# BPF.net
KiCad netlist of a schematic drawn in Altium Designer
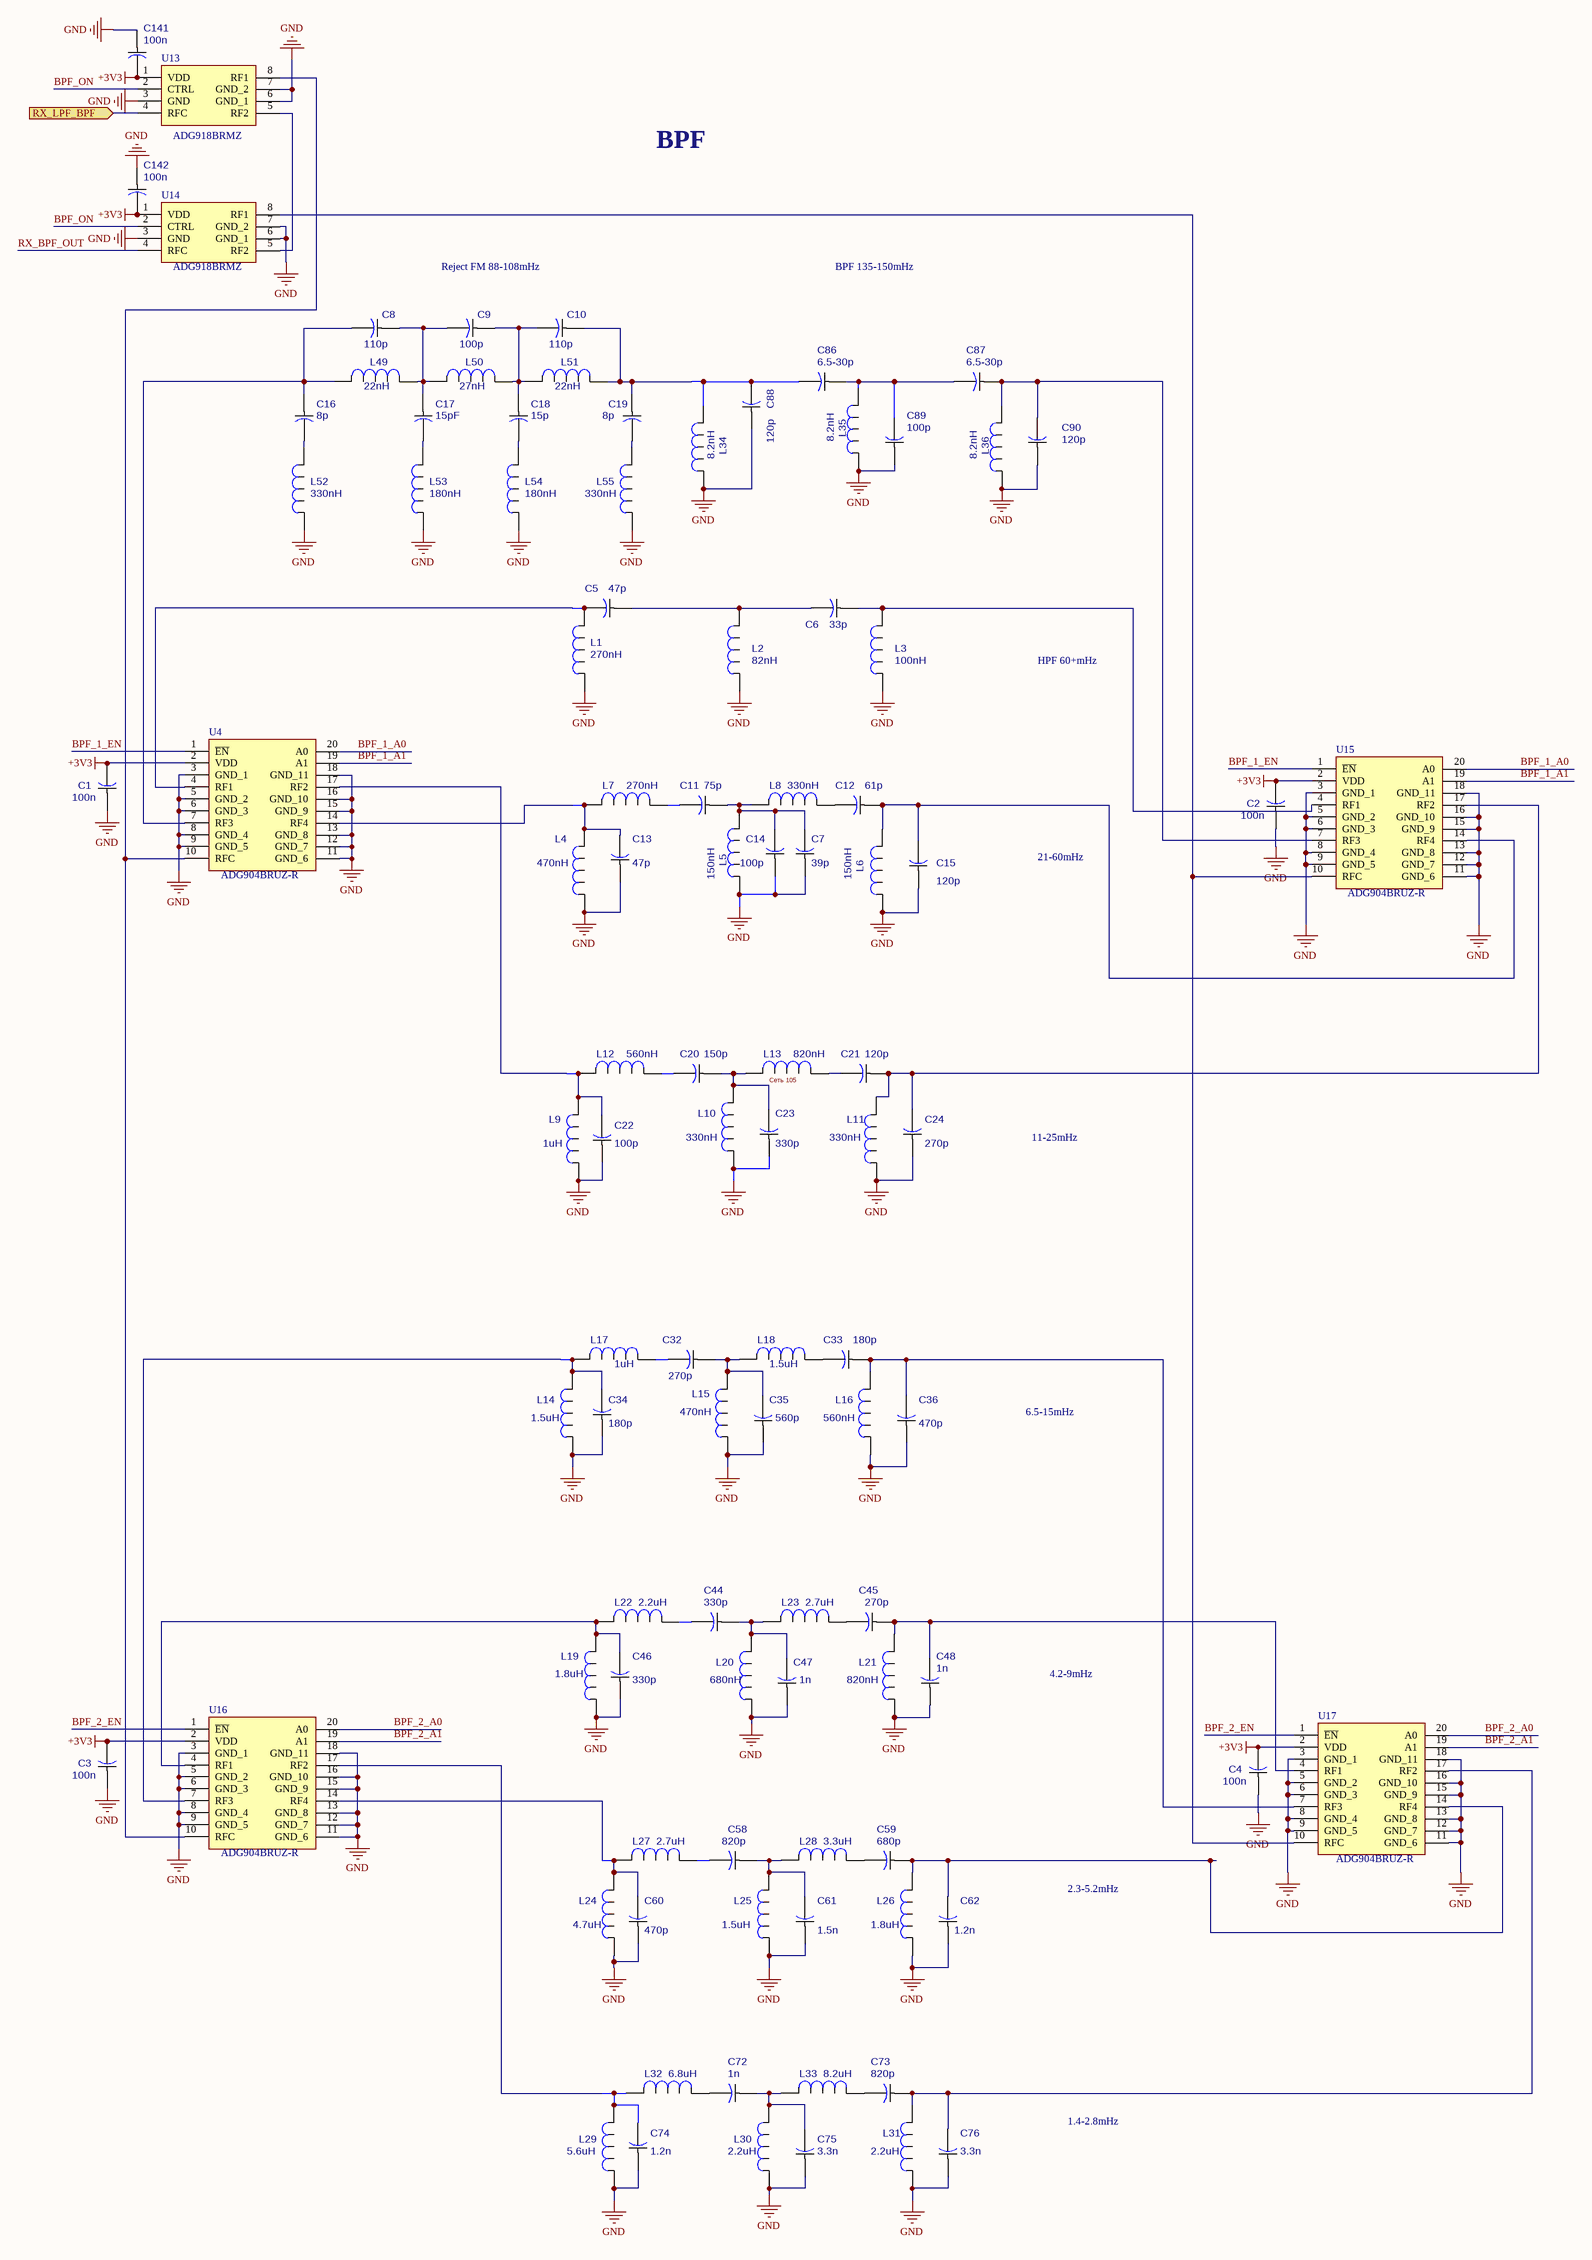
[diagram p0: BPF.SchDoc]

(export (version "E")
  (design (tool "Eeschema 10.0.6"))
  (components
    (comp (ref "C1")
      (value "100n")
      (footprint "CAP_0805")
      (description "CAP_0805")
      (libsource (lib "*") (part "CAP_0805"))
    )
    (comp (ref "C2")
      (value "100n")
      (footprint "CAP_0805")
      (description "CAP_0805")
      (libsource (lib "*") (part "CAP_0805"))
    )
    (comp (ref "C3")
      (value "100n")
      (footprint "CAP_0805")
      (description "CAP_0805")
      (libsource (lib "*") (part "CAP_0805"))
    )
    (comp (ref "C4")
      (value "100n")
      (footprint "CAP_0805")
      (description "CAP_0805")
      (libsource (lib "*") (part "CAP_0805"))
    )
    (comp (ref "C5")
      (value "47p")
      (footprint "CAP_0805")
      (description "CAP_0805")
      (libsource (lib "*") (part "CAP_0805"))
    )
    (comp (ref "C6")
      (value "33p")
      (footprint "CAP_0805")
      (description "CAP_0805")
      (libsource (lib "*") (part "CAP_0805"))
    )
    (comp (ref "C7")
      (value "39p")
      (footprint "CAP_0805")
      (description "CAP_0805")
      (libsource (lib "*") (part "CAP_0805"))
    )
    (comp (ref "C8")
      (value "110p")
      (footprint "CAP_0805")
      (description "CAP_0805")
      (libsource (lib "*") (part "CAP_0805"))
    )
    (comp (ref "C9")
      (value "100p")
      (footprint "CAP_0805")
      (description "CAP_0805")
      (libsource (lib "*") (part "CAP_0805"))
    )
    (comp (ref "C10")
      (value "110p")
      (footprint "CAP_0805")
      (description "CAP_0805")
      (libsource (lib "*") (part "CAP_0805"))
    )
    (comp (ref "C11")
      (value "75p")
      (footprint "CAP_0805")
      (description "CAP_0805")
      (libsource (lib "*") (part "CAP_0805"))
    )
    (comp (ref "C12")
      (value "61p")
      (footprint "CAP_0805")
      (description "CAP_0805")
      (libsource (lib "*") (part "CAP_0805"))
    )
    (comp (ref "C13")
      (value "47p")
      (footprint "CAP_0805")
      (description "CAP_0805")
      (libsource (lib "*") (part "CAP_0805"))
    )
    (comp (ref "C14")
      (value "100p")
      (footprint "CAP_0805")
      (description "CAP_0805")
      (libsource (lib "*") (part "CAP_0805"))
    )
    (comp (ref "C15")
      (value "120p")
      (footprint "CAP_0805")
      (description "CAP_0805")
      (libsource (lib "*") (part "CAP_0805"))
    )
    (comp (ref "C16")
      (value "8p")
      (footprint "CAP_0805")
      (description "CAP_0805")
      (libsource (lib "*") (part "CAP_0805"))
    )
    (comp (ref "C17")
      (value "15pF")
      (footprint "CAP_0805")
      (description "CAP_0805")
      (libsource (lib "*") (part "CAP_0805"))
    )
    (comp (ref "C18")
      (value "15p")
      (footprint "CAP_0805")
      (description "CAP_0805")
      (libsource (lib "*") (part "CAP_0805"))
    )
    (comp (ref "C19")
      (value "8p")
      (footprint "CAP_0805")
      (description "CAP_0805")
      (libsource (lib "*") (part "CAP_0805"))
    )
    (comp (ref "C20")
      (value "150p")
      (footprint "CAP_0805")
      (description "CAP_0805")
      (libsource (lib "*") (part "CAP_0805"))
    )
    (comp (ref "C21")
      (value "120p")
      (footprint "CAP_0805")
      (description "CAP_0805")
      (libsource (lib "*") (part "CAP_0805"))
    )
    (comp (ref "C22")
      (value "100p")
      (footprint "CAP_0805")
      (description "CAP_0805")
      (libsource (lib "*") (part "CAP_0805"))
    )
    (comp (ref "C23")
      (value "330p")
      (footprint "CAP_0805")
      (description "CAP_0805")
      (libsource (lib "*") (part "CAP_0805"))
    )
    (comp (ref "C24")
      (value "270p")
      (footprint "CAP_0805")
      (description "CAP_0805")
      (libsource (lib "*") (part "CAP_0805"))
    )
    (comp (ref "C32")
      (value "270p")
      (footprint "CAP_0805")
      (description "CAP_0805")
      (libsource (lib "*") (part "CAP_0805"))
    )
    (comp (ref "C33")
      (value "180p")
      (footprint "CAP_0805")
      (description "CAP_0805")
      (libsource (lib "*") (part "CAP_0805"))
    )
    (comp (ref "C34")
      (value "180p")
      (footprint "CAP_0805")
      (description "CAP_0805")
      (libsource (lib "*") (part "CAP_0805"))
    )
    (comp (ref "C35")
      (value "560p")
      (footprint "CAP_0805")
      (description "CAP_0805")
      (libsource (lib "*") (part "CAP_0805"))
    )
    (comp (ref "C36")
      (value "470p")
      (footprint "CAP_0805")
      (description "CAP_0805")
      (libsource (lib "*") (part "CAP_0805"))
    )
    (comp (ref "C44")
      (value "330p")
      (footprint "CAP_0805")
      (description "CAP_0805")
      (libsource (lib "*") (part "CAP_0805"))
    )
    (comp (ref "C45")
      (value "270p")
      (footprint "CAP_0805")
      (description "CAP_0805")
      (libsource (lib "*") (part "CAP_0805"))
    )
    (comp (ref "C46")
      (value "330p")
      (footprint "CAP_0805")
      (description "CAP_0805")
      (libsource (lib "*") (part "CAP_0805"))
    )
    (comp (ref "C47")
      (value "1n")
      (footprint "CAP_0805")
      (description "CAP_0805")
      (libsource (lib "*") (part "CAP_0805"))
    )
    (comp (ref "C48")
      (value "1n")
      (footprint "CAP_0805")
      (description "CAP_0805")
      (libsource (lib "*") (part "CAP_0805"))
    )
    (comp (ref "C58")
      (value "820p")
      (footprint "CAP_0805")
      (description "CAP_0805")
      (libsource (lib "*") (part "CAP_0805"))
    )
    (comp (ref "C59")
      (value "680p")
      (footprint "CAP_0805")
      (description "CAP_0805")
      (libsource (lib "*") (part "CAP_0805"))
    )
    (comp (ref "C60")
      (value "470p")
      (footprint "CAP_0805")
      (description "CAP_0805")
      (libsource (lib "*") (part "CAP_0805"))
    )
    (comp (ref "C61")
      (value "1.5n")
      (footprint "CAP_0805")
      (description "CAP_0805")
      (libsource (lib "*") (part "CAP_0805"))
    )
    (comp (ref "C62")
      (value "1.2n")
      (footprint "CAP_0805")
      (description "CAP_0805")
      (libsource (lib "*") (part "CAP_0805"))
    )
    (comp (ref "C72")
      (value "1n")
      (footprint "CAP_0805")
      (description "CAP_0805")
      (libsource (lib "*") (part "CAP_0805"))
    )
    (comp (ref "C73")
      (value "820p")
      (footprint "CAP_0805")
      (description "CAP_0805")
      (libsource (lib "*") (part "CAP_0805"))
    )
    (comp (ref "C74")
      (value "1.2n")
      (footprint "CAP_0805")
      (description "CAP_0805")
      (libsource (lib "*") (part "CAP_0805"))
    )
    (comp (ref "C75")
      (value "3.3n")
      (footprint "CAP_0805")
      (description "CAP_0805")
      (libsource (lib "*") (part "CAP_0805"))
    )
    (comp (ref "C76")
      (value "3.3n")
      (footprint "CAP_0805")
      (description "CAP_0805")
      (libsource (lib "*") (part "CAP_0805"))
    )
    (comp (ref "C86")
      (value "6.5-30p")
      (footprint "5025[2010]")
      (description "TZC3P300A110")
      (libsource (lib "*") (part "CAP_0805"))
    )
    (comp (ref "C87")
      (value "6.5-30p")
      (footprint "5025[2010]")
      (description "TZC3P300A110")
      (libsource (lib "*") (part "CAP_0805"))
    )
    (comp (ref "C88")
      (value "120p")
      (footprint "CAP_0805")
      (description "CAP_0805")
      (libsource (lib "*") (part "CAP_0805"))
    )
    (comp (ref "C89")
      (value "100p")
      (footprint "CAP_0805")
      (description "CAP_0805")
      (libsource (lib "*") (part "CAP_0805"))
    )
    (comp (ref "C90")
      (value "120p")
      (footprint "CAP_0805")
      (description "CAP_0805")
      (libsource (lib "*") (part "CAP_0805"))
    )
    (comp (ref "C141")
      (value "100n")
      (footprint "CAP_0805")
      (description "CAP_0805")
      (libsource (lib "*") (part "CAP_0805"))
    )
    (comp (ref "C142")
      (value "100n")
      (footprint "CAP_0805")
      (description "CAP_0805")
      (libsource (lib "*") (part "CAP_0805"))
    )
    (comp (ref "L1")
      (value "270nH")
      (footprint "IND_0805")
      (description "IND_0805")
      (libsource (lib "*") (part "IND_0805"))
    )
    (comp (ref "L2")
      (value "82nH")
      (footprint "IND_0805")
      (description "IND_0805")
      (libsource (lib "*") (part "IND_0805"))
    )
    (comp (ref "L3")
      (value "100nH")
      (footprint "IND_0805")
      (description "IND_0805")
      (libsource (lib "*") (part "IND_0805"))
    )
    (comp (ref "L4")
      (value "470nH")
      (footprint "IND_0805")
      (description "IND_0805")
      (libsource (lib "*") (part "IND_0805"))
    )
    (comp (ref "L5")
      (value "150nH")
      (footprint "IND_0805")
      (description "IND_0805")
      (libsource (lib "*") (part "IND_0805"))
    )
    (comp (ref "L6")
      (value "150nH")
      (footprint "IND_0805")
      (description "IND_0805")
      (libsource (lib "*") (part "IND_0805"))
    )
    (comp (ref "L7")
      (value "270nH")
      (footprint "IND_0805")
      (description "IND_0805")
      (libsource (lib "*") (part "IND_0805"))
    )
    (comp (ref "L8")
      (value "330nH")
      (footprint "IND_0805")
      (description "IND_0805")
      (libsource (lib "*") (part "IND_0805"))
    )
    (comp (ref "L9")
      (value "1uH")
      (footprint "IND_0805")
      (description "IND_0805")
      (libsource (lib "*") (part "IND_0805"))
    )
    (comp (ref "L10")
      (value "330nH")
      (footprint "IND_0805")
      (description "IND_0805")
      (libsource (lib "*") (part "IND_0805"))
    )
    (comp (ref "L11")
      (value "330nH")
      (footprint "IND_0805")
      (description "IND_0805")
      (libsource (lib "*") (part "IND_0805"))
    )
    (comp (ref "L12")
      (value "560nH")
      (footprint "IND_0805")
      (description "IND_0805")
      (libsource (lib "*") (part "IND_0805"))
    )
    (comp (ref "L13")
      (value "820nH")
      (footprint "IND_0805")
      (description "IND_0805")
      (libsource (lib "*") (part "IND_0805"))
    )
    (comp (ref "L14")
      (value "1.5uH")
      (footprint "IND_0805")
      (description "IND_0805")
      (libsource (lib "*") (part "IND_0805"))
    )
    (comp (ref "L15")
      (value "470nH")
      (footprint "IND_0805")
      (description "IND_0805")
      (libsource (lib "*") (part "IND_0805"))
    )
    (comp (ref "L16")
      (value "560nH")
      (footprint "IND_0805")
      (description "IND_0805")
      (libsource (lib "*") (part "IND_0805"))
    )
    (comp (ref "L17")
      (value "1uH")
      (footprint "IND_0805")
      (description "IND_0805")
      (libsource (lib "*") (part "IND_0805"))
    )
    (comp (ref "L18")
      (value "1.5uH")
      (footprint "IND_0805")
      (description "IND_0805")
      (libsource (lib "*") (part "IND_0805"))
    )
    (comp (ref "L19")
      (value "1.8uH")
      (footprint "IND_0805")
      (description "IND_0805")
      (libsource (lib "*") (part "IND_0805"))
    )
    (comp (ref "L20")
      (value "680nH")
      (footprint "IND_0805")
      (description "IND_0805")
      (libsource (lib "*") (part "IND_0805"))
    )
    (comp (ref "L21")
      (value "820nH")
      (footprint "IND_0805")
      (description "IND_0805")
      (libsource (lib "*") (part "IND_0805"))
    )
    (comp (ref "L22")
      (value "2.2uH")
      (footprint "IND_0805")
      (description "IND_0805")
      (libsource (lib "*") (part "IND_0805"))
    )
    (comp (ref "L23")
      (value "2.7uH")
      (footprint "IND_0805")
      (description "IND_0805")
      (libsource (lib "*") (part "IND_0805"))
    )
    (comp (ref "L24")
      (value "4.7uH")
      (footprint "IND_0805")
      (description "IND_0805")
      (libsource (lib "*") (part "IND_0805"))
    )
    (comp (ref "L25")
      (value "1.5uH")
      (footprint "IND_0805")
      (description "IND_0805")
      (libsource (lib "*") (part "IND_0805"))
    )
    (comp (ref "L26")
      (value "1.8uH")
      (footprint "IND_0805")
      (description "IND_0805")
      (libsource (lib "*") (part "IND_0805"))
    )
    (comp (ref "L27")
      (value "2.7uH")
      (footprint "IND_0805")
      (description "IND_0805")
      (libsource (lib "*") (part "IND_0805"))
    )
    (comp (ref "L28")
      (value "3.3uH")
      (footprint "IND_0805")
      (description "IND_0805")
      (libsource (lib "*") (part "IND_0805"))
    )
    (comp (ref "L29")
      (value "5.6uH")
      (footprint "IND_0805")
      (description "IND_0805")
      (libsource (lib "*") (part "IND_0805"))
    )
    (comp (ref "L30")
      (value "2.2uH")
      (footprint "IND_0805")
      (description "IND_0805")
      (libsource (lib "*") (part "IND_0805"))
    )
    (comp (ref "L31")
      (value "2.2uH")
      (footprint "IND_0805")
      (description "IND_0805")
      (libsource (lib "*") (part "IND_0805"))
    )
    (comp (ref "L32")
      (value "6.8uH")
      (footprint "IND_0805")
      (description "IND_0805")
      (libsource (lib "*") (part "IND_0805"))
    )
    (comp (ref "L33")
      (value "8.2uH")
      (footprint "IND_0805")
      (description "IND_0805")
      (libsource (lib "*") (part "IND_0805"))
    )
    (comp (ref "L34")
      (value "8.2nH")
      (footprint "IND_0805")
      (description "IND_0805")
      (libsource (lib "*") (part "IND_0805"))
    )
    (comp (ref "L35")
      (value "8.2nH")
      (footprint "IND_0805")
      (description "IND_0805")
      (libsource (lib "*") (part "IND_0805"))
    )
    (comp (ref "L36")
      (value "8.2nH")
      (footprint "IND_0805")
      (description "IND_0805")
      (libsource (lib "*") (part "IND_0805"))
    )
    (comp (ref "L49")
      (value "22nH")
      (footprint "IND_0805")
      (description "IND_0805")
      (libsource (lib "*") (part "IND_0805"))
    )
    (comp (ref "L50")
      (value "27nH")
      (footprint "IND_0805")
      (description "IND_0805")
      (libsource (lib "*") (part "IND_0805"))
    )
    (comp (ref "L51")
      (value "22nH")
      (footprint "IND_0805")
      (description "IND_0805")
      (libsource (lib "*") (part "IND_0805"))
    )
    (comp (ref "L52")
      (value "330nH")
      (footprint "IND_0805")
      (description "IND_0805")
      (libsource (lib "*") (part "IND_0805"))
    )
    (comp (ref "L53")
      (value "180nH")
      (footprint "IND_0805")
      (description "IND_0805")
      (libsource (lib "*") (part "IND_0805"))
    )
    (comp (ref "L54")
      (value "180nH")
      (footprint "IND_0805")
      (description "IND_0805")
      (libsource (lib "*") (part "IND_0805"))
    )
    (comp (ref "L55")
      (value "330nH")
      (footprint "IND_0805")
      (description "IND_0805")
      (libsource (lib "*") (part "IND_0805"))
    )
    (comp (ref "U4")
      (value "ADG904BRUZ-R")
      (footprint "SamacSys:SOP65P640X120-20N")
      (description "Integrated Circuit")
      (fields
        (field (name "MOUSER PART NUMBER") "584-ADG904BRUZ-R")
        (field (name "RS PART NUMBER") "5385019P")
      )
      (libsource (lib "*") (part "ADG904BRUZ-R"))
    )
    (comp (ref "U13")
      (value "ADG918BRMZ")
      (footprint "SamacSys:SOP65P490X110-8N")
      (description "Integrated Circuit")
      (fields (field (name "MOUSER PART NUMBER") "584-ADG918BRMZ") (field (name "RS PART NUMBER") "4969212P"))
      (libsource (lib "*") (part "ADG918BRMZ"))
    )
    (comp (ref "U14")
      (value "ADG918BRMZ")
      (footprint "SamacSys:SOP65P490X110-8N")
      (description "Integrated Circuit")
      (fields (field (name "MOUSER PART NUMBER") "584-ADG918BRMZ") (field (name "RS PART NUMBER") "4969212P"))
      (libsource (lib "*") (part "ADG918BRMZ"))
    )
    (comp (ref "U15")
      (value "ADG904BRUZ-R")
      (footprint "SamacSys:SOP65P640X120-20N")
      (description "Integrated Circuit")
      (fields
        (field (name "MOUSER PART NUMBER") "584-ADG904BRUZ-R")
        (field (name "RS PART NUMBER") "5385019P")
      )
      (libsource (lib "*") (part "ADG904BRUZ-R"))
    )
    (comp (ref "U16")
      (value "ADG904BRUZ-R")
      (footprint "SamacSys:SOP65P640X120-20N")
      (description "Integrated Circuit")
      (fields
        (field (name "MOUSER PART NUMBER") "584-ADG904BRUZ-R")
        (field (name "RS PART NUMBER") "5385019P")
      )
      (libsource (lib "*") (part "ADG904BRUZ-R"))
    )
    (comp (ref "U17")
      (value "ADG904BRUZ-R")
      (footprint "SamacSys:SOP65P640X120-20N")
      (description "Integrated Circuit")
      (fields
        (field (name "MOUSER PART NUMBER") "584-ADG904BRUZ-R")
        (field (name "RS PART NUMBER") "5385019P")
      )
      (libsource (lib "*") (part "ADG904BRUZ-R"))
    )
  )
  (nets
    (net (code "1") (name "+3V3") (class "Default")
      (node (ref "C1") (pin "2") (pinfunction "2_2") (pintype "passive"))
      (node (ref "C141") (pin "2") (pinfunction "2_2") (pintype "passive"))
      (node (ref "C142") (pin "2") (pinfunction "2_2") (pintype "passive"))
      (node (ref "C2") (pin "2") (pinfunction "2_2") (pintype "passive"))
      (node (ref "C3") (pin "2") (pinfunction "2_2") (pintype "passive"))
      (node (ref "C4") (pin "2") (pinfunction "2_2") (pintype "passive"))
      (node (ref "U13") (pin "1") (pinfunction "VDD_1") (pintype "power_in"))
      (node (ref "U14") (pin "1") (pinfunction "VDD_1") (pintype "power_in"))
      (node (ref "U15") (pin "2") (pinfunction "VDD_2") (pintype "passive"))
      (node (ref "U16") (pin "2") (pinfunction "VDD_2") (pintype "passive"))
      (node (ref "U17") (pin "2") (pinfunction "VDD_2") (pintype "passive"))
      (node (ref "U4") (pin "2") (pinfunction "VDD_2") (pintype "passive"))
    )
    (net (code "2") (name "/BPF_1_A0") (class "Default")
      (node (ref "U15") (pin "20") (pinfunction "A0_20") (pintype "passive"))
      (node (ref "U4") (pin "20") (pinfunction "A0_20") (pintype "passive"))
    )
    (net (code "3") (name "/BPF_1_A1") (class "Default")
      (node (ref "U15") (pin "19") (pinfunction "A1_19") (pintype "passive"))
      (node (ref "U4") (pin "19") (pinfunction "A1_19") (pintype "passive"))
    )
    (net (code "4") (name "/BPF_1_EN") (class "Default")
      (node (ref "U15") (pin "1") (pinfunction "~{EN}_1") (pintype "passive"))
      (node (ref "U4") (pin "1") (pinfunction "~{EN}_1") (pintype "passive"))
    )
    (net (code "5") (name "/BPF_2_A0") (class "Default")
      (node (ref "U16") (pin "20") (pinfunction "A0_20") (pintype "passive"))
      (node (ref "U17") (pin "20") (pinfunction "A0_20") (pintype "passive"))
    )
    (net (code "6") (name "/BPF_2_A1") (class "Default")
      (node (ref "U16") (pin "19") (pinfunction "A1_19") (pintype "passive"))
      (node (ref "U17") (pin "19") (pinfunction "A1_19") (pintype "passive"))
    )
    (net (code "7") (name "/BPF_2_EN") (class "Default")
      (node (ref "U16") (pin "1") (pinfunction "~{EN}_1") (pintype "passive"))
      (node (ref "U17") (pin "1") (pinfunction "~{EN}_1") (pintype "passive"))
    )
    (net (code "8") (name "/BPF_ON") (class "Default")
      (node (ref "U13") (pin "2") (pinfunction "CTRL_2") (pintype "passive"))
      (node (ref "U14") (pin "2") (pinfunction "CTRL_2") (pintype "passive"))
    )
    (net (code "9") (name "/RX_BPF_OUT") (class "Default")
      (node (ref "U14") (pin "4") (pinfunction "RFC_4") (pintype "passive"))
    )
    (net (code "10") (name "/RX_LPF_BPF") (class "Default")
      (node (ref "U13") (pin "4") (pinfunction "RFC_4") (pintype "passive"))
    )
    (net (code "11") (name "/Сеть 105") (class "Default")
      (node (ref "C20") (pin "1") (pinfunction "1_1") (pintype "passive"))
      (node (ref "C23") (pin "2") (pinfunction "2_2") (pintype "passive"))
      (node (ref "L10") (pin "2") (pinfunction "2_2") (pintype "passive"))
      (node (ref "L13") (pin "1") (pinfunction "1_1") (pintype "passive"))
    )
    (net (code "12") (name "GND") (class "Default")
      (node (ref "C1") (pin "1") (pinfunction "1_1") (pintype "passive"))
      (node (ref "C13") (pin "1") (pinfunction "1_1") (pintype "passive"))
      (node (ref "C14") (pin "1") (pinfunction "1_1") (pintype "passive"))
      (node (ref "C141") (pin "1") (pinfunction "1_1") (pintype "passive"))
      (node (ref "C142") (pin "1") (pinfunction "1_1") (pintype "passive"))
      (node (ref "C15") (pin "1") (pinfunction "1_1") (pintype "passive"))
      (node (ref "C2") (pin "1") (pinfunction "1_1") (pintype "passive"))
      (node (ref "C22") (pin "1") (pinfunction "1_1") (pintype "passive"))
      (node (ref "C23") (pin "1") (pinfunction "1_1") (pintype "passive"))
      (node (ref "C24") (pin "1") (pinfunction "1_1") (pintype "passive"))
      (node (ref "C3") (pin "1") (pinfunction "1_1") (pintype "passive"))
      (node (ref "C34") (pin "1") (pinfunction "1_1") (pintype "passive"))
      (node (ref "C35") (pin "1") (pinfunction "1_1") (pintype "passive"))
      (node (ref "C36") (pin "1") (pinfunction "1_1") (pintype "passive"))
      (node (ref "C4") (pin "1") (pinfunction "1_1") (pintype "passive"))
      (node (ref "C46") (pin "1") (pinfunction "1_1") (pintype "passive"))
      (node (ref "C47") (pin "1") (pinfunction "1_1") (pintype "passive"))
      (node (ref "C48") (pin "1") (pinfunction "1_1") (pintype "passive"))
      (node (ref "C60") (pin "1") (pinfunction "1_1") (pintype "passive"))
      (node (ref "C61") (pin "1") (pinfunction "1_1") (pintype "passive"))
      (node (ref "C62") (pin "1") (pinfunction "1_1") (pintype "passive"))
      (node (ref "C7") (pin "1") (pinfunction "1_1") (pintype "passive"))
      (node (ref "C74") (pin "1") (pinfunction "1_1") (pintype "passive"))
      (node (ref "C75") (pin "1") (pinfunction "1_1") (pintype "passive"))
      (node (ref "C76") (pin "1") (pinfunction "1_1") (pintype "passive"))
      (node (ref "C88") (pin "1") (pinfunction "1_1") (pintype "passive"))
      (node (ref "C89") (pin "1") (pinfunction "1_1") (pintype "passive"))
      (node (ref "C90") (pin "1") (pinfunction "1_1") (pintype "passive"))
      (node (ref "L1") (pin "1") (pinfunction "1_1") (pintype "passive"))
      (node (ref "L10") (pin "1") (pinfunction "1_1") (pintype "passive"))
      (node (ref "L11") (pin "1") (pinfunction "1_1") (pintype "passive"))
      (node (ref "L14") (pin "1") (pinfunction "1_1") (pintype "passive"))
      (node (ref "L15") (pin "1") (pinfunction "1_1") (pintype "passive"))
      (node (ref "L16") (pin "1") (pinfunction "1_1") (pintype "passive"))
      (node (ref "L19") (pin "1") (pinfunction "1_1") (pintype "passive"))
      (node (ref "L2") (pin "1") (pinfunction "1_1") (pintype "passive"))
      (node (ref "L20") (pin "1") (pinfunction "1_1") (pintype "passive"))
      (node (ref "L21") (pin "1") (pinfunction "1_1") (pintype "passive"))
      (node (ref "L24") (pin "1") (pinfunction "1_1") (pintype "passive"))
      (node (ref "L25") (pin "1") (pinfunction "1_1") (pintype "passive"))
      (node (ref "L26") (pin "1") (pinfunction "1_1") (pintype "passive"))
      (node (ref "L29") (pin "1") (pinfunction "1_1") (pintype "passive"))
      (node (ref "L3") (pin "1") (pinfunction "1_1") (pintype "passive"))
      (node (ref "L30") (pin "1") (pinfunction "1_1") (pintype "passive"))
      (node (ref "L31") (pin "1") (pinfunction "1_1") (pintype "passive"))
      (node (ref "L34") (pin "1") (pinfunction "1_1") (pintype "passive"))
      (node (ref "L35") (pin "1") (pinfunction "1_1") (pintype "passive"))
      (node (ref "L36") (pin "1") (pinfunction "1_1") (pintype "passive"))
      (node (ref "L4") (pin "1") (pinfunction "1_1") (pintype "passive"))
      (node (ref "L5") (pin "1") (pinfunction "1_1") (pintype "passive"))
      (node (ref "L52") (pin "1") (pinfunction "1_1") (pintype "passive"))
      (node (ref "L53") (pin "1") (pinfunction "1_1") (pintype "passive"))
      (node (ref "L54") (pin "1") (pinfunction "1_1") (pintype "passive"))
      (node (ref "L55") (pin "1") (pinfunction "1_1") (pintype "passive"))
      (node (ref "L6") (pin "1") (pinfunction "1_1") (pintype "passive"))
      (node (ref "L9") (pin "1") (pinfunction "1_1") (pintype "passive"))
      (node (ref "U13") (pin "3") (pinfunction "GND_3") (pintype "power_in"))
      (node (ref "U13") (pin "6") (pinfunction "GND_1_6") (pintype "power_in"))
      (node (ref "U13") (pin "7") (pinfunction "GND_2_7") (pintype "power_in"))
      (node (ref "U14") (pin "3") (pinfunction "GND_3") (pintype "power_in"))
      (node (ref "U14") (pin "6") (pinfunction "GND_1_6") (pintype "power_in"))
      (node (ref "U14") (pin "7") (pinfunction "GND_2_7") (pintype "power_in"))
      (node (ref "U15") (pin "11") (pinfunction "GND_6_11") (pintype "passive"))
      (node (ref "U15") (pin "12") (pinfunction "GND_7_12") (pintype "passive"))
      (node (ref "U15") (pin "13") (pinfunction "GND_8_13") (pintype "passive"))
      (node (ref "U15") (pin "15") (pinfunction "GND_9_15") (pintype "passive"))
      (node (ref "U15") (pin "16") (pinfunction "GND_10_16") (pintype "passive"))
      (node (ref "U15") (pin "18") (pinfunction "GND_11_18") (pintype "passive"))
      (node (ref "U15") (pin "3") (pinfunction "GND_1_3") (pintype "passive"))
      (node (ref "U15") (pin "5") (pinfunction "GND_2_5") (pintype "passive"))
      (node (ref "U15") (pin "6") (pinfunction "GND_3_6") (pintype "passive"))
      (node (ref "U15") (pin "8") (pinfunction "GND_4_8") (pintype "passive"))
      (node (ref "U15") (pin "9") (pinfunction "GND_5_9") (pintype "passive"))
      (node (ref "U16") (pin "11") (pinfunction "GND_6_11") (pintype "passive"))
      (node (ref "U16") (pin "12") (pinfunction "GND_7_12") (pintype "passive"))
      (node (ref "U16") (pin "13") (pinfunction "GND_8_13") (pintype "passive"))
      (node (ref "U16") (pin "15") (pinfunction "GND_9_15") (pintype "passive"))
      (node (ref "U16") (pin "16") (pinfunction "GND_10_16") (pintype "passive"))
      (node (ref "U16") (pin "18") (pinfunction "GND_11_18") (pintype "passive"))
      (node (ref "U16") (pin "3") (pinfunction "GND_1_3") (pintype "passive"))
      (node (ref "U16") (pin "5") (pinfunction "GND_2_5") (pintype "passive"))
      (node (ref "U16") (pin "6") (pinfunction "GND_3_6") (pintype "passive"))
      (node (ref "U16") (pin "8") (pinfunction "GND_4_8") (pintype "passive"))
      (node (ref "U16") (pin "9") (pinfunction "GND_5_9") (pintype "passive"))
      (node (ref "U17") (pin "11") (pinfunction "GND_6_11") (pintype "passive"))
      (node (ref "U17") (pin "12") (pinfunction "GND_7_12") (pintype "passive"))
      (node (ref "U17") (pin "13") (pinfunction "GND_8_13") (pintype "passive"))
      (node (ref "U17") (pin "15") (pinfunction "GND_9_15") (pintype "passive"))
      (node (ref "U17") (pin "16") (pinfunction "GND_10_16") (pintype "passive"))
      (node (ref "U17") (pin "18") (pinfunction "GND_11_18") (pintype "passive"))
      (node (ref "U17") (pin "3") (pinfunction "GND_1_3") (pintype "passive"))
      (node (ref "U17") (pin "5") (pinfunction "GND_2_5") (pintype "passive"))
      (node (ref "U17") (pin "6") (pinfunction "GND_3_6") (pintype "passive"))
      (node (ref "U17") (pin "8") (pinfunction "GND_4_8") (pintype "passive"))
      (node (ref "U17") (pin "9") (pinfunction "GND_5_9") (pintype "passive"))
      (node (ref "U4") (pin "11") (pinfunction "GND_6_11") (pintype "passive"))
      (node (ref "U4") (pin "12") (pinfunction "GND_7_12") (pintype "passive"))
      (node (ref "U4") (pin "13") (pinfunction "GND_8_13") (pintype "passive"))
      (node (ref "U4") (pin "15") (pinfunction "GND_9_15") (pintype "passive"))
      (node (ref "U4") (pin "16") (pinfunction "GND_10_16") (pintype "passive"))
      (node (ref "U4") (pin "18") (pinfunction "GND_11_18") (pintype "passive"))
      (node (ref "U4") (pin "3") (pinfunction "GND_1_3") (pintype "passive"))
      (node (ref "U4") (pin "5") (pinfunction "GND_2_5") (pintype "passive"))
      (node (ref "U4") (pin "6") (pinfunction "GND_3_6") (pintype "passive"))
      (node (ref "U4") (pin "8") (pinfunction "GND_4_8") (pintype "passive"))
      (node (ref "U4") (pin "9") (pinfunction "GND_5_9") (pintype "passive"))
    )
    (net (code "13") (name "Net-(C5-Pad1)") (class "Default")
      (node (ref "C5") (pin "1") (pinfunction "1_1") (pintype "passive"))
      (node (ref "C6") (pin "2") (pinfunction "2_2") (pintype "passive"))
      (node (ref "L2") (pin "2") (pinfunction "2_2") (pintype "passive"))
    )
    (net (code "14") (name "Net-(C10-Pad1)") (class "Default")
      (node (ref "C10") (pin "1") (pinfunction "1_1") (pintype "passive"))
      (node (ref "C19") (pin "1") (pinfunction "1_1") (pintype "passive"))
      (node (ref "C86") (pin "2") (pinfunction "2_2") (pintype "passive"))
      (node (ref "C88") (pin "2") (pinfunction "2_2") (pintype "passive"))
      (node (ref "L34") (pin "2") (pinfunction "2_2") (pintype "passive"))
      (node (ref "L51") (pin "2") (pinfunction "2_2") (pintype "passive"))
    )
    (net (code "15") (name "Net-(C10-Pad2)") (class "Default")
      (node (ref "C10") (pin "2") (pinfunction "2_2") (pintype "passive"))
      (node (ref "C18") (pin "1") (pinfunction "1_1") (pintype "passive"))
      (node (ref "C9") (pin "1") (pinfunction "1_1") (pintype "passive"))
      (node (ref "L50") (pin "2") (pinfunction "2_2") (pintype "passive"))
      (node (ref "L51") (pin "1") (pinfunction "1_1") (pintype "passive"))
    )
    (net (code "16") (name "Net-(C11-Pad1)") (class "Default")
      (node (ref "C11") (pin "1") (pinfunction "1_1") (pintype "passive"))
      (node (ref "C14") (pin "2") (pinfunction "2_2") (pintype "passive"))
      (node (ref "C7") (pin "2") (pinfunction "2_2") (pintype "passive"))
      (node (ref "L5") (pin "2") (pinfunction "2_2") (pintype "passive"))
      (node (ref "L8") (pin "1") (pinfunction "1_1") (pintype "passive"))
    )
    (net (code "17") (name "Net-(C11-Pad2)") (class "Default")
      (node (ref "C11") (pin "2") (pinfunction "2_2") (pintype "passive"))
      (node (ref "L7") (pin "2") (pinfunction "2_2") (pintype "passive"))
    )
    (net (code "18") (name "Net-(C12-Pad2)") (class "Default")
      (node (ref "C12") (pin "2") (pinfunction "2_2") (pintype "passive"))
      (node (ref "L8") (pin "2") (pinfunction "2_2") (pintype "passive"))
    )
    (net (code "19") (name "Net-(C16-Pad2)") (class "Default")
      (node (ref "C16") (pin "2") (pinfunction "2_2") (pintype "passive"))
      (node (ref "L52") (pin "2") (pinfunction "2_2") (pintype "passive"))
    )
    (net (code "20") (name "Net-(C17-Pad1)") (class "Default")
      (node (ref "C17") (pin "1") (pinfunction "1_1") (pintype "passive"))
      (node (ref "C8") (pin "1") (pinfunction "1_1") (pintype "passive"))
      (node (ref "C9") (pin "2") (pinfunction "2_2") (pintype "passive"))
      (node (ref "L49") (pin "2") (pinfunction "2_2") (pintype "passive"))
      (node (ref "L50") (pin "1") (pinfunction "1_1") (pintype "passive"))
    )
    (net (code "21") (name "Net-(C17-Pad2)") (class "Default")
      (node (ref "C17") (pin "2") (pinfunction "2_2") (pintype "passive"))
      (node (ref "L53") (pin "2") (pinfunction "2_2") (pintype "passive"))
    )
    (net (code "22") (name "Net-(C18-Pad2)") (class "Default")
      (node (ref "C18") (pin "2") (pinfunction "2_2") (pintype "passive"))
      (node (ref "L54") (pin "2") (pinfunction "2_2") (pintype "passive"))
    )
    (net (code "23") (name "Net-(C19-Pad2)") (class "Default")
      (node (ref "C19") (pin "2") (pinfunction "2_2") (pintype "passive"))
      (node (ref "L55") (pin "2") (pinfunction "2_2") (pintype "passive"))
    )
    (net (code "24") (name "Net-(C20-Pad2)") (class "Default")
      (node (ref "C20") (pin "2") (pinfunction "2_2") (pintype "passive"))
      (node (ref "L12") (pin "2") (pinfunction "2_2") (pintype "passive"))
    )
    (net (code "25") (name "Net-(C21-Pad2)") (class "Default")
      (node (ref "C21") (pin "2") (pinfunction "2_2") (pintype "passive"))
      (node (ref "L13") (pin "2") (pinfunction "2_2") (pintype "passive"))
    )
    (net (code "26") (name "Net-(C32-Pad1)") (class "Default")
      (node (ref "C32") (pin "1") (pinfunction "1_1") (pintype "passive"))
      (node (ref "C35") (pin "2") (pinfunction "2_2") (pintype "passive"))
      (node (ref "L15") (pin "2") (pinfunction "2_2") (pintype "passive"))
      (node (ref "L18") (pin "1") (pinfunction "1_1") (pintype "passive"))
    )
    (net (code "27") (name "Net-(C32-Pad2)") (class "Default")
      (node (ref "C32") (pin "2") (pinfunction "2_2") (pintype "passive"))
      (node (ref "L17") (pin "2") (pinfunction "2_2") (pintype "passive"))
    )
    (net (code "28") (name "Net-(C33-Pad2)") (class "Default")
      (node (ref "C33") (pin "2") (pinfunction "2_2") (pintype "passive"))
      (node (ref "L18") (pin "2") (pinfunction "2_2") (pintype "passive"))
    )
    (net (code "29") (name "Net-(C44-Pad1)") (class "Default")
      (node (ref "C44") (pin "1") (pinfunction "1_1") (pintype "passive"))
      (node (ref "C47") (pin "2") (pinfunction "2_2") (pintype "passive"))
      (node (ref "L20") (pin "2") (pinfunction "2_2") (pintype "passive"))
      (node (ref "L23") (pin "1") (pinfunction "1_1") (pintype "passive"))
    )
    (net (code "30") (name "Net-(C44-Pad2)") (class "Default")
      (node (ref "C44") (pin "2") (pinfunction "2_2") (pintype "passive"))
      (node (ref "L22") (pin "2") (pinfunction "2_2") (pintype "passive"))
    )
    (net (code "31") (name "Net-(C45-Pad2)") (class "Default")
      (node (ref "C45") (pin "2") (pinfunction "2_2") (pintype "passive"))
      (node (ref "L23") (pin "2") (pinfunction "2_2") (pintype "passive"))
    )
    (net (code "32") (name "Net-(C58-Pad1)") (class "Default")
      (node (ref "C58") (pin "1") (pinfunction "1_1") (pintype "passive"))
      (node (ref "C61") (pin "2") (pinfunction "2_2") (pintype "passive"))
      (node (ref "L25") (pin "2") (pinfunction "2_2") (pintype "passive"))
      (node (ref "L28") (pin "1") (pinfunction "1_1") (pintype "passive"))
    )
    (net (code "33") (name "Net-(C58-Pad2)") (class "Default")
      (node (ref "C58") (pin "2") (pinfunction "2_2") (pintype "passive"))
      (node (ref "L27") (pin "2") (pinfunction "2_2") (pintype "passive"))
    )
    (net (code "34") (name "Net-(C59-Pad2)") (class "Default")
      (node (ref "C59") (pin "2") (pinfunction "2_2") (pintype "passive"))
      (node (ref "L28") (pin "2") (pinfunction "2_2") (pintype "passive"))
    )
    (net (code "35") (name "Net-(C72-Pad1)") (class "Default")
      (node (ref "C72") (pin "1") (pinfunction "1_1") (pintype "passive"))
      (node (ref "C75") (pin "2") (pinfunction "2_2") (pintype "passive"))
      (node (ref "L30") (pin "2") (pinfunction "2_2") (pintype "passive"))
      (node (ref "L33") (pin "1") (pinfunction "1_1") (pintype "passive"))
    )
    (net (code "36") (name "Net-(C72-Pad2)") (class "Default")
      (node (ref "C72") (pin "2") (pinfunction "2_2") (pintype "passive"))
      (node (ref "L32") (pin "2") (pinfunction "2_2") (pintype "passive"))
    )
    (net (code "37") (name "Net-(C73-Pad2)") (class "Default")
      (node (ref "C73") (pin "2") (pinfunction "2_2") (pintype "passive"))
      (node (ref "L33") (pin "2") (pinfunction "2_2") (pintype "passive"))
    )
    (net (code "38") (name "Net-(C86-Pad1)") (class "Default")
      (node (ref "C86") (pin "1") (pinfunction "1_1") (pintype "passive"))
      (node (ref "C87") (pin "2") (pinfunction "2_2") (pintype "passive"))
      (node (ref "C89") (pin "2") (pinfunction "2_2") (pintype "passive"))
      (node (ref "L35") (pin "2") (pinfunction "2_2") (pintype "passive"))
    )
    (net (code "39") (name "Net-(U4-RF1)") (class "Default")
      (node (ref "C5") (pin "2") (pinfunction "2_2") (pintype "passive"))
      (node (ref "L1") (pin "2") (pinfunction "2_2") (pintype "passive"))
      (node (ref "U4") (pin "4") (pinfunction "RF1_4") (pintype "passive"))
    )
    (net (code "40") (name "Net-(U4-RF2)") (class "Default")
      (node (ref "C22") (pin "2") (pinfunction "2_2") (pintype "passive"))
      (node (ref "L12") (pin "1") (pinfunction "1_1") (pintype "passive"))
      (node (ref "L9") (pin "2") (pinfunction "2_2") (pintype "passive"))
      (node (ref "U4") (pin "17") (pinfunction "RF2_17") (pintype "passive"))
    )
    (net (code "41") (name "Net-(U4-RF3)") (class "Default")
      (node (ref "C16") (pin "1") (pinfunction "1_1") (pintype "passive"))
      (node (ref "C8") (pin "2") (pinfunction "2_2") (pintype "passive"))
      (node (ref "L49") (pin "1") (pinfunction "1_1") (pintype "passive"))
      (node (ref "U4") (pin "7") (pinfunction "RF3_7") (pintype "passive"))
    )
    (net (code "42") (name "Net-(U4-RF4)") (class "Default")
      (node (ref "C13") (pin "2") (pinfunction "2_2") (pintype "passive"))
      (node (ref "L4") (pin "2") (pinfunction "2_2") (pintype "passive"))
      (node (ref "L7") (pin "1") (pinfunction "1_1") (pintype "passive"))
      (node (ref "U4") (pin "14") (pinfunction "RF4_14") (pintype "passive"))
    )
    (net (code "43") (name "Net-(U13-RF1)") (class "Default")
      (node (ref "U13") (pin "8") (pinfunction "RF1_8") (pintype "passive"))
      (node (ref "U16") (pin "10") (pinfunction "RFC_10") (pintype "passive"))
      (node (ref "U4") (pin "10") (pinfunction "RFC_10") (pintype "passive"))
    )
    (net (code "44") (name "Net-(U13-RF2)") (class "Default")
      (node (ref "U13") (pin "5") (pinfunction "RF2_5") (pintype "passive"))
      (node (ref "U14") (pin "5") (pinfunction "RF2_5") (pintype "passive"))
    )
    (net (code "45") (name "Net-(U14-RF1)") (class "Default")
      (node (ref "U14") (pin "8") (pinfunction "RF1_8") (pintype "passive"))
      (node (ref "U15") (pin "10") (pinfunction "RFC_10") (pintype "passive"))
      (node (ref "U17") (pin "10") (pinfunction "RFC_10") (pintype "passive"))
    )
    (net (code "46") (name "Net-(U15-RF1)") (class "Default")
      (node (ref "C6") (pin "1") (pinfunction "1_1") (pintype "passive"))
      (node (ref "L3") (pin "2") (pinfunction "2_2") (pintype "passive"))
      (node (ref "U15") (pin "4") (pinfunction "RF1_4") (pintype "passive"))
    )
    (net (code "47") (name "Net-(U15-RF2)") (class "Default")
      (node (ref "C21") (pin "1") (pinfunction "1_1") (pintype "passive"))
      (node (ref "C24") (pin "2") (pinfunction "2_2") (pintype "passive"))
      (node (ref "L11") (pin "2") (pinfunction "2_2") (pintype "passive"))
      (node (ref "U15") (pin "17") (pinfunction "RF2_17") (pintype "passive"))
    )
    (net (code "48") (name "Net-(U15-RF3)") (class "Default")
      (node (ref "C87") (pin "1") (pinfunction "1_1") (pintype "passive"))
      (node (ref "C90") (pin "2") (pinfunction "2_2") (pintype "passive"))
      (node (ref "L36") (pin "2") (pinfunction "2_2") (pintype "passive"))
      (node (ref "U15") (pin "7") (pinfunction "RF3_7") (pintype "passive"))
    )
    (net (code "49") (name "Net-(U15-RF4)") (class "Default")
      (node (ref "C12") (pin "1") (pinfunction "1_1") (pintype "passive"))
      (node (ref "C15") (pin "2") (pinfunction "2_2") (pintype "passive"))
      (node (ref "L6") (pin "2") (pinfunction "2_2") (pintype "passive"))
      (node (ref "U15") (pin "14") (pinfunction "RF4_14") (pintype "passive"))
    )
    (net (code "50") (name "Net-(U16-RF1)") (class "Default")
      (node (ref "C46") (pin "2") (pinfunction "2_2") (pintype "passive"))
      (node (ref "L19") (pin "2") (pinfunction "2_2") (pintype "passive"))
      (node (ref "L22") (pin "1") (pinfunction "1_1") (pintype "passive"))
      (node (ref "U16") (pin "4") (pinfunction "RF1_4") (pintype "passive"))
    )
    (net (code "51") (name "Net-(U16-RF2)") (class "Default")
      (node (ref "C74") (pin "2") (pinfunction "2_2") (pintype "passive"))
      (node (ref "L29") (pin "2") (pinfunction "2_2") (pintype "passive"))
      (node (ref "L32") (pin "1") (pinfunction "1_1") (pintype "passive"))
      (node (ref "U16") (pin "17") (pinfunction "RF2_17") (pintype "passive"))
    )
    (net (code "52") (name "Net-(U16-RF3)") (class "Default")
      (node (ref "C34") (pin "2") (pinfunction "2_2") (pintype "passive"))
      (node (ref "L14") (pin "2") (pinfunction "2_2") (pintype "passive"))
      (node (ref "L17") (pin "1") (pinfunction "1_1") (pintype "passive"))
      (node (ref "U16") (pin "7") (pinfunction "RF3_7") (pintype "passive"))
    )
    (net (code "53") (name "Net-(U16-RF4)") (class "Default")
      (node (ref "C60") (pin "2") (pinfunction "2_2") (pintype "passive"))
      (node (ref "L24") (pin "2") (pinfunction "2_2") (pintype "passive"))
      (node (ref "L27") (pin "1") (pinfunction "1_1") (pintype "passive"))
      (node (ref "U16") (pin "14") (pinfunction "RF4_14") (pintype "passive"))
    )
    (net (code "54") (name "Net-(U17-RF1)") (class "Default")
      (node (ref "C45") (pin "1") (pinfunction "1_1") (pintype "passive"))
      (node (ref "C48") (pin "2") (pinfunction "2_2") (pintype "passive"))
      (node (ref "L21") (pin "2") (pinfunction "2_2") (pintype "passive"))
      (node (ref "U17") (pin "4") (pinfunction "RF1_4") (pintype "passive"))
    )
    (net (code "55") (name "Net-(U17-RF2)") (class "Default")
      (node (ref "C73") (pin "1") (pinfunction "1_1") (pintype "passive"))
      (node (ref "C76") (pin "2") (pinfunction "2_2") (pintype "passive"))
      (node (ref "L31") (pin "2") (pinfunction "2_2") (pintype "passive"))
      (node (ref "U17") (pin "17") (pinfunction "RF2_17") (pintype "passive"))
    )
    (net (code "56") (name "Net-(U17-RF3)") (class "Default")
      (node (ref "C33") (pin "1") (pinfunction "1_1") (pintype "passive"))
      (node (ref "C36") (pin "2") (pinfunction "2_2") (pintype "passive"))
      (node (ref "L16") (pin "2") (pinfunction "2_2") (pintype "passive"))
      (node (ref "U17") (pin "7") (pinfunction "RF3_7") (pintype "passive"))
    )
    (net (code "57") (name "Net-(U17-RF4)") (class "Default")
      (node (ref "C59") (pin "1") (pinfunction "1_1") (pintype "passive"))
      (node (ref "C62") (pin "2") (pinfunction "2_2") (pintype "passive"))
      (node (ref "L26") (pin "2") (pinfunction "2_2") (pintype "passive"))
      (node (ref "U17") (pin "14") (pinfunction "RF4_14") (pintype "passive"))
    )
  )
)
